# Access_System_Bmduino_V1_2.net
KiCad netlist of a schematic drawn in Altium Designer
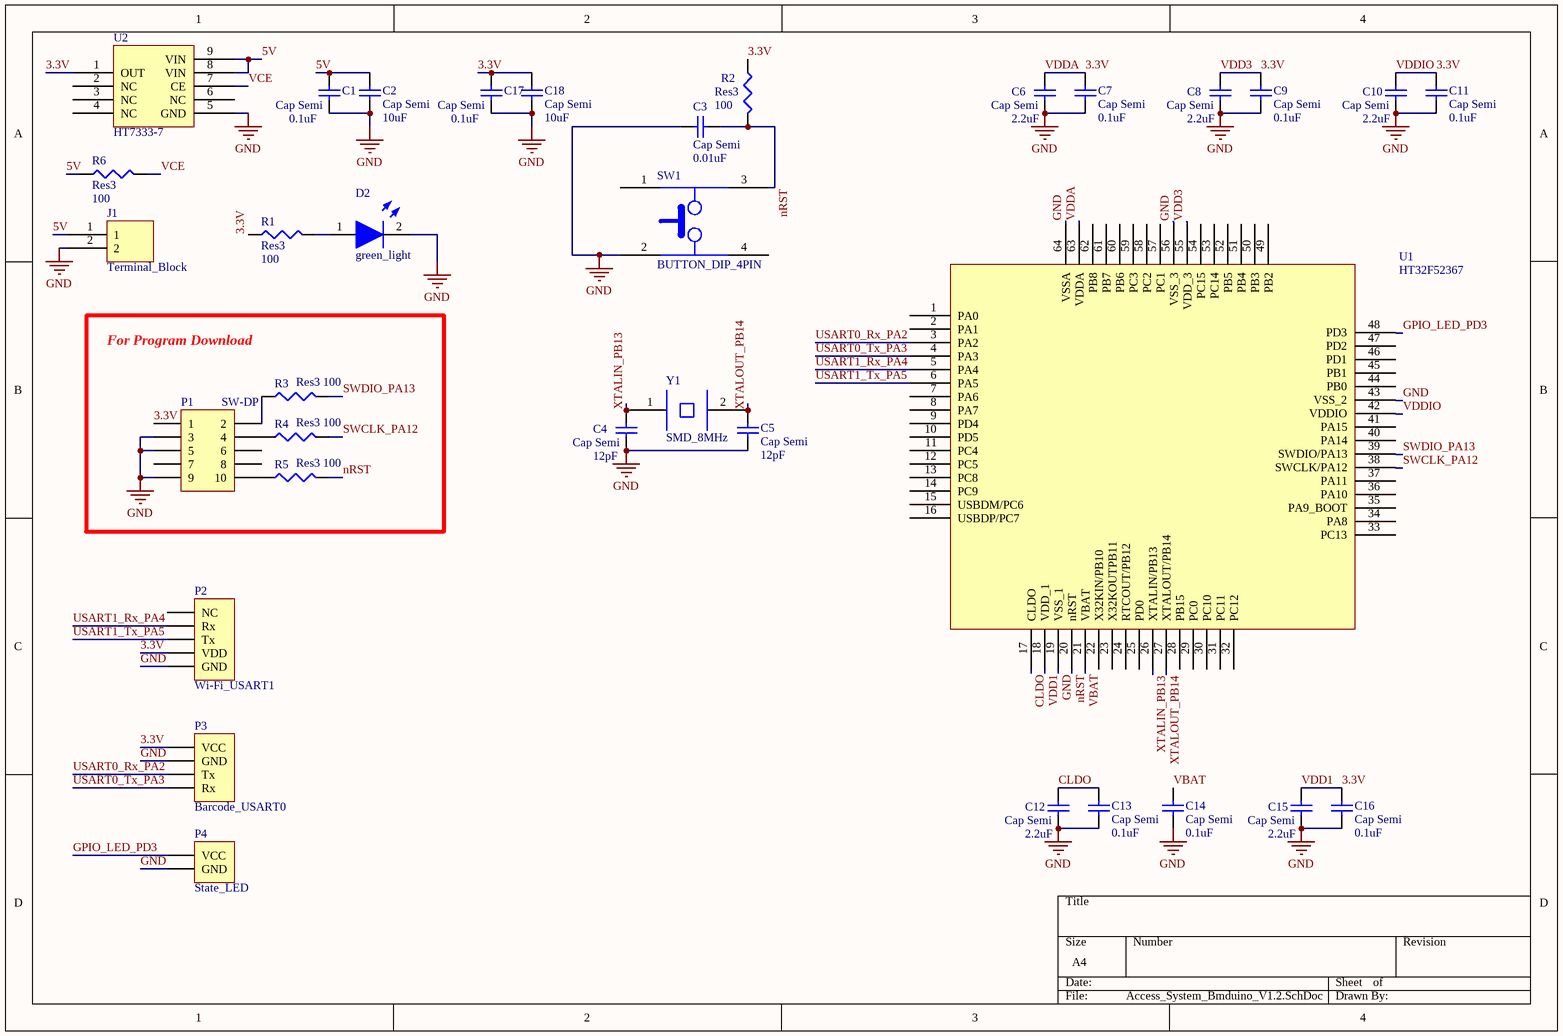
[diagram p0: Access_System_Bmduino_V1.2.SchDoc]

(export (version "E")
  (design (tool "Eeschema 10.0.6"))
  (components
    (comp (ref "C1")
      (value "Cap Semi")
      (footprint "1608[0603]")
      (description "Capacitor (Semiconductor SIM Model)")
      (fields (field (name "ALTIUM_VALUE") "0.1uF") (field (name "PUBLISHER") "Altium Limited"))
      (libsource (lib "Miscellaneous Devices") (part "Cap Semi"))
    )
    (comp (ref "C2")
      (value "Cap Semi")
      (footprint "1608[0603]")
      (description "Capacitor (Semiconductor SIM Model)")
      (fields (field (name "ALTIUM_VALUE") "10uF") (field (name "PUBLISHER") "Altium Limited"))
      (libsource (lib "Miscellaneous Devices") (part "Cap Semi"))
    )
    (comp (ref "C3")
      (value "Cap Semi")
      (footprint "1608[0603]")
      (description "Capacitor (Semiconductor SIM Model)")
      (fields (field (name "ALTIUM_VALUE") "0.01uF") (field (name "PUBLISHER") "Altium Limited"))
      (libsource (lib "Miscellaneous Devices") (part "Cap Semi"))
    )
    (comp (ref "C4")
      (value "Cap Semi")
      (footprint "1608[0603]")
      (description "Capacitor (Semiconductor SIM Model)")
      (fields (field (name "ALTIUM_VALUE") "12pF") (field (name "PUBLISHER") "Altium Limited"))
      (libsource (lib "Miscellaneous Devices") (part "Cap Semi"))
    )
    (comp (ref "C5")
      (value "Cap Semi")
      (footprint "1608[0603]")
      (description "Capacitor (Semiconductor SIM Model)")
      (fields (field (name "ALTIUM_VALUE") "12pF") (field (name "PUBLISHER") "Altium Limited"))
      (libsource (lib "Miscellaneous Devices") (part "Cap Semi"))
    )
    (comp (ref "C6")
      (value "Cap Semi")
      (footprint "1608[0603]")
      (description "Capacitor (Semiconductor SIM Model)")
      (fields (field (name "ALTIUM_VALUE") "2.2uF") (field (name "PUBLISHER") "Altium Limited"))
      (libsource (lib "Miscellaneous Devices") (part "Cap Semi"))
    )
    (comp (ref "C7")
      (value "Cap Semi")
      (footprint "1608[0603]")
      (description "Capacitor (Semiconductor SIM Model)")
      (fields (field (name "ALTIUM_VALUE") "0.1uF") (field (name "PUBLISHER") "Altium Limited"))
      (libsource (lib "Miscellaneous Devices") (part "Cap Semi"))
    )
    (comp (ref "C8")
      (value "Cap Semi")
      (footprint "1608[0603]")
      (description "Capacitor (Semiconductor SIM Model)")
      (fields (field (name "ALTIUM_VALUE") "2.2uF") (field (name "PUBLISHER") "Altium Limited"))
      (libsource (lib "Miscellaneous Devices") (part "Cap Semi"))
    )
    (comp (ref "C9")
      (value "Cap Semi")
      (footprint "1608[0603]")
      (description "Capacitor (Semiconductor SIM Model)")
      (fields (field (name "ALTIUM_VALUE") "0.1uF") (field (name "PUBLISHER") "Altium Limited"))
      (libsource (lib "Miscellaneous Devices") (part "Cap Semi"))
    )
    (comp (ref "C10")
      (value "Cap Semi")
      (footprint "1608[0603]")
      (description "Capacitor (Semiconductor SIM Model)")
      (fields (field (name "ALTIUM_VALUE") "2.2uF") (field (name "PUBLISHER") "Altium Limited"))
      (libsource (lib "Miscellaneous Devices") (part "Cap Semi"))
    )
    (comp (ref "C11")
      (value "Cap Semi")
      (footprint "1608[0603]")
      (description "Capacitor (Semiconductor SIM Model)")
      (fields (field (name "ALTIUM_VALUE") "0.1uF") (field (name "PUBLISHER") "Altium Limited"))
      (libsource (lib "Miscellaneous Devices") (part "Cap Semi"))
    )
    (comp (ref "C12")
      (value "Cap Semi")
      (footprint "1608[0603]")
      (description "Capacitor (Semiconductor SIM Model)")
      (fields (field (name "ALTIUM_VALUE") "2.2uF") (field (name "PUBLISHER") "Altium Limited"))
      (libsource (lib "Miscellaneous Devices") (part "Cap Semi"))
    )
    (comp (ref "C13")
      (value "Cap Semi")
      (footprint "1608[0603]")
      (description "Capacitor (Semiconductor SIM Model)")
      (fields (field (name "ALTIUM_VALUE") "0.1uF") (field (name "PUBLISHER") "Altium Limited"))
      (libsource (lib "Miscellaneous Devices") (part "Cap Semi"))
    )
    (comp (ref "C14")
      (value "Cap Semi")
      (footprint "1608[0603]")
      (description "Capacitor (Semiconductor SIM Model)")
      (fields (field (name "ALTIUM_VALUE") "0.1uF") (field (name "PUBLISHER") "Altium Limited"))
      (libsource (lib "Miscellaneous Devices") (part "Cap Semi"))
    )
    (comp (ref "C15")
      (value "Cap Semi")
      (footprint "1608[0603]")
      (description "Capacitor (Semiconductor SIM Model)")
      (fields (field (name "ALTIUM_VALUE") "2.2uF") (field (name "PUBLISHER") "Altium Limited"))
      (libsource (lib "Miscellaneous Devices") (part "Cap Semi"))
    )
    (comp (ref "C16")
      (value "Cap Semi")
      (footprint "1608[0603]")
      (description "Capacitor (Semiconductor SIM Model)")
      (fields (field (name "ALTIUM_VALUE") "0.1uF") (field (name "PUBLISHER") "Altium Limited"))
      (libsource (lib "Miscellaneous Devices") (part "Cap Semi"))
    )
    (comp (ref "C17")
      (value "Cap Semi")
      (footprint "1608[0603]")
      (description "Capacitor (Semiconductor SIM Model)")
      (fields (field (name "ALTIUM_VALUE") "0.1uF") (field (name "PUBLISHER") "Altium Limited"))
      (libsource (lib "Miscellaneous Devices") (part "Cap Semi"))
    )
    (comp (ref "C18")
      (value "Cap Semi")
      (footprint "1608[0603]")
      (description "Capacitor (Semiconductor SIM Model)")
      (fields (field (name "ALTIUM_VALUE") "10uF") (field (name "PUBLISHER") "Altium Limited"))
      (libsource (lib "Miscellaneous Devices") (part "Cap Semi"))
    )
    (comp (ref "D2")
      (value "green_light")
      (footprint "LED_Green")
      (libsource (lib "Lab_share") (part "LED_Green"))
    )
    (comp (ref "J1")
      (value "Terminal_Block")
      (footprint "terminal block")
      (libsource (lib "Lab_share") (part "Terminal Block"))
    )
    (comp (ref "P1")
      (value "SW-DP")
      (footprint "HDR2X5")
      (description "Header, 5-Pin, Dual row")
      (fields (field (name "PUBLISHER") "Altium Limited"))
      (libsource (lib "Miscellaneous Connectors") (part "Header 5X2"))
    )
    (comp (ref "P2")
      (value "Wi-Fi_USART1")
      (footprint "HDR1X5")
      (description "Header, 5-Pin")
      (fields (field (name "PUBLISHER") "Altium Limited"))
      (libsource (lib "Miscellaneous Connectors") (part "Header 5"))
    )
    (comp (ref "P3")
      (value "Barcode_USART0")
      (footprint "HDR1X4")
      (description "Header, 4-Pin")
      (fields (field (name "PUBLISHER") "Altium Limited"))
      (libsource (lib "Miscellaneous Connectors") (part "Header 4"))
    )
    (comp (ref "P4")
      (value "State_LED")
      (footprint "HDR1X2")
      (description "Header, 2-Pin")
      (fields (field (name "PUBLISHER") "Altium Limited"))
      (libsource (lib "Miscellaneous Connectors") (part "Header 2"))
    )
    (comp (ref "R1")
      (value "Res3")
      (footprint "J1-0603")
      (description "Resistor")
      (fields (field (name "ALTIUM_VALUE") "100") (field (name "PUBLISHER") "Altium Limited"))
      (libsource (lib "Miscellaneous Devices") (part "Res3"))
    )
    (comp (ref "R2")
      (value "Res3")
      (footprint "J1-0603")
      (description "Resistor")
      (fields (field (name "ALTIUM_VALUE") "100") (field (name "PUBLISHER") "Altium Limited"))
      (libsource (lib "Miscellaneous Devices") (part "Res3"))
    )
    (comp (ref "R3")
      (value "Res3")
      (footprint "J1-0603")
      (description "Resistor")
      (fields (field (name "ALTIUM_VALUE") "100") (field (name "PUBLISHER") "Altium Limited"))
      (libsource (lib "Miscellaneous Devices") (part "Res3"))
    )
    (comp (ref "R4")
      (value "Res3")
      (footprint "J1-0603")
      (description "Resistor")
      (fields (field (name "ALTIUM_VALUE") "100") (field (name "PUBLISHER") "Altium Limited"))
      (libsource (lib "Miscellaneous Devices") (part "Res3"))
    )
    (comp (ref "R5")
      (value "Res3")
      (footprint "J1-0603")
      (description "Resistor")
      (fields (field (name "ALTIUM_VALUE") "100") (field (name "PUBLISHER") "Altium Limited"))
      (libsource (lib "Miscellaneous Devices") (part "Res3"))
    )
    (comp (ref "R6")
      (value "Res3")
      (footprint "J1-0603")
      (description "Resistor")
      (fields (field (name "ALTIUM_VALUE") "100") (field (name "PUBLISHER") "Altium Limited"))
      (libsource (lib "Miscellaneous Devices") (part "Res3"))
    )
    (comp (ref "SW1")
      (value "BUTTON_DIP_4PIN")
      (footprint "Push_Button")
      (libsource (lib "Lab_share") (part "Push_Button"))
    )
    (comp (ref "U1")
      (value "HT32F52367")
      (footprint "HT32H52367")
      (libsource (lib "Lab_share") (part "HT32F52367"))
    )
    (comp (ref "U2") (value "HT7333-7") (footprint "HT7333") (libsource (lib "Lab_share") (part "HT7333")))
    (comp (ref "Y1")
      (value "SMD_8MHz")
      (footprint "Quartz-Crystal-8MHz")
      (libsource (lib "Lab_share") (part "Quartz_Crystal_8MHz"))
    )
  )
  (nets
    (net (code "1") (name "/3.3V") (class "Default")
      (node (ref "C10") (pin "1") (pinfunction "1_1") (pintype "passive"))
      (node (ref "C11") (pin "2") (pinfunction "2_2") (pintype "passive"))
      (node (ref "C15") (pin "1") (pinfunction "1_1") (pintype "passive"))
      (node (ref "C16") (pin "2") (pinfunction "2_2") (pintype "passive"))
      (node (ref "C17") (pin "2") (pinfunction "2_2") (pintype "passive"))
      (node (ref "C18") (pin "2") (pinfunction "2_2") (pintype "passive"))
      (node (ref "C6") (pin "1") (pinfunction "1_1") (pintype "passive"))
      (node (ref "C7") (pin "2") (pinfunction "2_2") (pintype "passive"))
      (node (ref "C8") (pin "1") (pinfunction "1_1") (pintype "passive"))
      (node (ref "C9") (pin "2") (pinfunction "2_2") (pintype "passive"))
      (node (ref "P1") (pin "1") (pinfunction "1_1") (pintype "passive"))
      (node (ref "P2") (pin "4") (pinfunction "VDD_4") (pintype "passive"))
      (node (ref "P3") (pin "1") (pinfunction "VCC_1") (pintype "passive"))
      (node (ref "R1") (pin "1") (pinfunction "1_1") (pintype "passive"))
      (node (ref "R2") (pin "1") (pinfunction "1_1") (pintype "passive"))
      (node (ref "U1") (pin "18") (pinfunction "VDD_1_18") (pintype "passive"))
      (node (ref "U1") (pin "42") (pinfunction "VDDIO_42") (pintype "passive"))
      (node (ref "U1") (pin "55") (pinfunction "VDD_3_55") (pintype "passive"))
      (node (ref "U1") (pin "63") (pinfunction "VDDA_63") (pintype "passive"))
      (node (ref "U2") (pin "1") (pinfunction "OUT_1") (pintype "passive"))
    )
    (net (code "2") (name "/5V") (class "Default")
      (node (ref "C1") (pin "2") (pinfunction "2_2") (pintype "passive"))
      (node (ref "C2") (pin "2") (pinfunction "2_2") (pintype "passive"))
      (node (ref "J1") (pin "1") (pinfunction "1_1") (pintype "passive"))
      (node (ref "R6") (pin "1") (pinfunction "1_1") (pintype "passive"))
      (node (ref "U2") (pin "8") (pinfunction "VIN_8") (pintype "passive"))
      (node (ref "U2") (pin "9") (pinfunction "VIN_9") (pintype "passive"))
    )
    (net (code "3") (name "/CLDO") (class "Default")
      (node (ref "C12") (pin "1") (pinfunction "1_1") (pintype "passive"))
      (node (ref "C13") (pin "2") (pinfunction "2_2") (pintype "passive"))
      (node (ref "U1") (pin "17") (pinfunction "CLDO_17") (pintype "passive"))
    )
    (net (code "4") (name "/GPIO_LED_PD3") (class "Default")
      (node (ref "P4") (pin "1") (pinfunction "VCC_1") (pintype "passive"))
      (node (ref "U1") (pin "48") (pinfunction "PD3_48") (pintype "passive"))
    )
    (net (code "5") (name "/SWCLK_PA12") (class "Default")
      (node (ref "R4") (pin "2") (pinfunction "2_2") (pintype "passive"))
      (node (ref "U1") (pin "38") (pinfunction "SWCLK/PA12_38") (pintype "passive"))
    )
    (net (code "6") (name "/SWDIO_PA13") (class "Default")
      (node (ref "R3") (pin "2") (pinfunction "2_2") (pintype "passive"))
      (node (ref "U1") (pin "39") (pinfunction "SWDIO/PA13_39") (pintype "passive"))
    )
    (net (code "7") (name "/USART0_Rx_PA2") (class "Default")
      (node (ref "P3") (pin "3") (pinfunction "Tx_3") (pintype "passive"))
      (node (ref "U1") (pin "3") (pinfunction "PA2_3") (pintype "passive"))
    )
    (net (code "8") (name "/USART0_Tx_PA3") (class "Default")
      (node (ref "P3") (pin "4") (pinfunction "Rx_4") (pintype "passive"))
      (node (ref "U1") (pin "4") (pinfunction "PA3_4") (pintype "passive"))
    )
    (net (code "9") (name "/USART1_Rx_PA4") (class "Default")
      (node (ref "P2") (pin "2") (pinfunction "Rx_2") (pintype "passive"))
      (node (ref "U1") (pin "5") (pinfunction "PA4_5") (pintype "passive"))
    )
    (net (code "10") (name "/USART1_Tx_PA5") (class "Default")
      (node (ref "P2") (pin "3") (pinfunction "Tx_3") (pintype "passive"))
      (node (ref "U1") (pin "6") (pinfunction "PA5_6") (pintype "passive"))
    )
    (net (code "11") (name "/VBAT") (class "Default")
      (node (ref "C14") (pin "2") (pinfunction "2_2") (pintype "passive"))
      (node (ref "U1") (pin "21") (pinfunction "VBAT_21") (pintype "passive"))
    )
    (net (code "12") (name "/VCE") (class "Default")
      (node (ref "R6") (pin "2") (pinfunction "2_2") (pintype "passive"))
      (node (ref "U2") (pin "7") (pinfunction "CE_7") (pintype "passive"))
    )
    (net (code "13") (name "/XTALIN_PB13") (class "Default")
      (node (ref "C4") (pin "1") (pinfunction "1_1") (pintype "passive"))
      (node (ref "U1") (pin "26") (pinfunction "XTALIN/PB13_26") (pintype "passive"))
      (node (ref "Y1") (pin "1") (pintype "passive"))
    )
    (net (code "14") (name "/XTALOUT_PB14") (class "Default")
      (node (ref "C5") (pin "2") (pinfunction "2_2") (pintype "passive"))
      (node (ref "U1") (pin "27") (pinfunction "XTALOUT/PB14_27") (pintype "passive"))
      (node (ref "Y1") (pin "2") (pintype "passive"))
    )
    (net (code "15") (name "/nRST") (class "Default")
      (node (ref "C3") (pin "1") (pinfunction "1_1") (pintype "passive"))
      (node (ref "R2") (pin "2") (pinfunction "2_2") (pintype "passive"))
      (node (ref "R5") (pin "2") (pinfunction "2_2") (pintype "passive"))
      (node (ref "SW1") (pin "3") (pintype "passive"))
      (node (ref "U1") (pin "20") (pinfunction "nRST_20") (pintype "passive"))
    )
    (net (code "16") (name "GND") (class "Default")
      (node (ref "C1") (pin "1") (pinfunction "1_1") (pintype "passive"))
      (node (ref "C10") (pin "2") (pinfunction "2_2") (pintype "passive"))
      (node (ref "C11") (pin "1") (pinfunction "1_1") (pintype "passive"))
      (node (ref "C12") (pin "2") (pinfunction "2_2") (pintype "passive"))
      (node (ref "C13") (pin "1") (pinfunction "1_1") (pintype "passive"))
      (node (ref "C14") (pin "1") (pinfunction "1_1") (pintype "passive"))
      (node (ref "C15") (pin "2") (pinfunction "2_2") (pintype "passive"))
      (node (ref "C16") (pin "1") (pinfunction "1_1") (pintype "passive"))
      (node (ref "C17") (pin "1") (pinfunction "1_1") (pintype "passive"))
      (node (ref "C18") (pin "1") (pinfunction "1_1") (pintype "passive"))
      (node (ref "C2") (pin "1") (pinfunction "1_1") (pintype "passive"))
      (node (ref "C3") (pin "2") (pinfunction "2_2") (pintype "passive"))
      (node (ref "C4") (pin "2") (pinfunction "2_2") (pintype "passive"))
      (node (ref "C5") (pin "1") (pinfunction "1_1") (pintype "passive"))
      (node (ref "C6") (pin "2") (pinfunction "2_2") (pintype "passive"))
      (node (ref "C7") (pin "1") (pinfunction "1_1") (pintype "passive"))
      (node (ref "C8") (pin "2") (pinfunction "2_2") (pintype "passive"))
      (node (ref "C9") (pin "1") (pinfunction "1_1") (pintype "passive"))
      (node (ref "D2") (pin "2") (pintype "passive"))
      (node (ref "J1") (pin "2") (pinfunction "2_2") (pintype "passive"))
      (node (ref "P1") (pin "3") (pinfunction "3_3") (pintype "passive"))
      (node (ref "P1") (pin "5") (pinfunction "5_5") (pintype "passive"))
      (node (ref "P1") (pin "9") (pinfunction "9_9") (pintype "passive"))
      (node (ref "P2") (pin "5") (pinfunction "GND_5") (pintype "passive"))
      (node (ref "P3") (pin "2") (pinfunction "GND_2") (pintype "passive"))
      (node (ref "P4") (pin "2") (pinfunction "GND_2") (pintype "passive"))
      (node (ref "SW1") (pin "2") (pintype "passive"))
      (node (ref "U1") (pin "19") (pinfunction "VSS_1_19") (pintype "passive"))
      (node (ref "U1") (pin "43") (pinfunction "VSS_2_43") (pintype "passive"))
      (node (ref "U1") (pin "56") (pinfunction "VSS_3_56") (pintype "passive"))
      (node (ref "U1") (pin "64") (pinfunction "VSSA_64") (pintype "passive"))
      (node (ref "U2") (pin "5") (pinfunction "GND_5") (pintype "passive"))
    )
    (net (code "17") (name "Net-(D2-Pad1)") (class "Default")
      (node (ref "D2") (pin "1") (pintype "passive"))
      (node (ref "R1") (pin "2") (pinfunction "2_2") (pintype "passive"))
    )
    (net (code "18") (name "Net-(P1-Pad2)") (class "Default")
      (node (ref "P1") (pin "2") (pinfunction "2_2") (pintype "passive"))
      (node (ref "R3") (pin "1") (pinfunction "1_1") (pintype "passive"))
    )
    (net (code "19") (name "Net-(P1-Pad4)") (class "Default")
      (node (ref "P1") (pin "4") (pinfunction "4_4") (pintype "passive"))
      (node (ref "R4") (pin "1") (pinfunction "1_1") (pintype "passive"))
    )
    (net (code "20") (name "Net-(P1-Pad10)") (class "Default")
      (node (ref "P1") (pin "10") (pinfunction "10_10") (pintype "passive"))
      (node (ref "R5") (pin "1") (pinfunction "1_1") (pintype "passive"))
    )
    (net (code "21") (name "unconnected-(P1-Pad6)") (class "Default")
      (node (ref "P1") (pin "6") (pinfunction "6_6") (pintype "passive"))
    )
    (net (code "22") (name "unconnected-(P1-Pad7)") (class "Default")
      (node (ref "P1") (pin "7") (pinfunction "7_7") (pintype "passive"))
    )
    (net (code "23") (name "unconnected-(P1-Pad8)") (class "Default")
      (node (ref "P1") (pin "8") (pinfunction "8_8") (pintype "passive"))
    )
    (net (code "24") (name "unconnected-(P2-NC-Pad1)") (class "Default")
      (node (ref "P2") (pin "1") (pinfunction "NC_1") (pintype "passive"))
    )
    (net (code "25") (name "unconnected-(SW1-Pad1)") (class "Default")
      (node (ref "SW1") (pin "1") (pintype "passive"))
    )
    (net (code "26") (name "unconnected-(SW1-Pad4)") (class "Default")
      (node (ref "SW1") (pin "4") (pintype "passive"))
    )
    (net (code "27") (name "unconnected-(U1-PA0-Pad1)") (class "Default")
      (node (ref "U1") (pin "1") (pinfunction "PA0_1") (pintype "passive"))
    )
    (net (code "28") (name "unconnected-(U1-PA1-Pad2)") (class "Default")
      (node (ref "U1") (pin "2") (pinfunction "PA1_2") (pintype "passive"))
    )
    (net (code "29") (name "unconnected-(U1-PA6-Pad7)") (class "Default")
      (node (ref "U1") (pin "7") (pinfunction "PA6_7") (pintype "passive"))
    )
    (net (code "30") (name "unconnected-(U1-PA7-Pad8)") (class "Default")
      (node (ref "U1") (pin "8") (pinfunction "PA7_8") (pintype "passive"))
    )
    (net (code "31") (name "unconnected-(U1-PA8-Pad34)") (class "Default")
      (node (ref "U1") (pin "34") (pinfunction "PA8_34") (pintype "passive"))
    )
    (net (code "32") (name "unconnected-(U1-PA9_BOOT-Pad35)") (class "Default")
      (node (ref "U1") (pin "35") (pinfunction "PA9_BOOT_35") (pintype "passive"))
    )
    (net (code "33") (name "unconnected-(U1-PA10-Pad36)") (class "Default")
      (node (ref "U1") (pin "36") (pinfunction "PA10_36") (pintype "passive"))
    )
    (net (code "34") (name "unconnected-(U1-PA11-Pad37)") (class "Default")
      (node (ref "U1") (pin "37") (pinfunction "PA11_37") (pintype "passive"))
    )
    (net (code "35") (name "unconnected-(U1-PA14-Pad40)") (class "Default")
      (node (ref "U1") (pin "40") (pinfunction "PA14_40") (pintype "passive"))
    )
    (net (code "36") (name "unconnected-(U1-PA15-Pad41)") (class "Default")
      (node (ref "U1") (pin "41") (pinfunction "PA15_41") (pintype "passive"))
    )
    (net (code "37") (name "unconnected-(U1-PB0-Pad44)") (class "Default")
      (node (ref "U1") (pin "44") (pinfunction "PB0_44") (pintype "passive"))
    )
    (net (code "38") (name "unconnected-(U1-PB1-Pad45)") (class "Default")
      (node (ref "U1") (pin "45") (pinfunction "PB1_45") (pintype "passive"))
    )
    (net (code "39") (name "unconnected-(U1-PB2-Pad49)") (class "Default")
      (node (ref "U1") (pin "49") (pinfunction "PB2_49") (pintype "passive"))
    )
    (net (code "40") (name "unconnected-(U1-PB3-Pad50)") (class "Default")
      (node (ref "U1") (pin "50") (pinfunction "PB3_50") (pintype "passive"))
    )
    (net (code "41") (name "unconnected-(U1-PB4-Pad51)") (class "Default")
      (node (ref "U1") (pin "51") (pinfunction "PB4_51") (pintype "passive"))
    )
    (net (code "42") (name "unconnected-(U1-PB5-Pad52)") (class "Default")
      (node (ref "U1") (pin "52") (pinfunction "PB5_52") (pintype "passive"))
    )
    (net (code "43") (name "unconnected-(U1-PB6-Pad60)") (class "Default")
      (node (ref "U1") (pin "60") (pinfunction "PB6_60") (pintype "passive"))
    )
    (net (code "44") (name "unconnected-(U1-PB7-Pad61)") (class "Default")
      (node (ref "U1") (pin "61") (pinfunction "PB7_61") (pintype "passive"))
    )
    (net (code "45") (name "unconnected-(U1-PB8-Pad62)") (class "Default")
      (node (ref "U1") (pin "62") (pinfunction "PB8_62") (pintype "passive"))
    )
    (net (code "46") (name "unconnected-(U1-PB15-Pad28)") (class "Default")
      (node (ref "U1") (pin "28") (pinfunction "PB15_28") (pintype "passive"))
    )
    (net (code "47") (name "unconnected-(U1-PC0-Pad29)") (class "Default")
      (node (ref "U1") (pin "29") (pinfunction "PC0_29") (pintype "passive"))
    )
    (net (code "48") (name "unconnected-(U1-PC1-Pad57)") (class "Default")
      (node (ref "U1") (pin "57") (pinfunction "PC1_57") (pintype "passive"))
    )
    (net (code "49") (name "unconnected-(U1-PC2-Pad58)") (class "Default")
      (node (ref "U1") (pin "58") (pinfunction "PC2_58") (pintype "passive"))
    )
    (net (code "50") (name "unconnected-(U1-PC3-Pad59)") (class "Default")
      (node (ref "U1") (pin "59") (pinfunction "PC3_59") (pintype "passive"))
    )
    (net (code "51") (name "unconnected-(U1-PC4-Pad11)") (class "Default")
      (node (ref "U1") (pin "11") (pinfunction "PC4_11") (pintype "passive"))
    )
    (net (code "52") (name "unconnected-(U1-PC5-Pad12)") (class "Default")
      (node (ref "U1") (pin "12") (pinfunction "PC5_12") (pintype "passive"))
    )
    (net (code "53") (name "unconnected-(U1-PC8-Pad13)") (class "Default")
      (node (ref "U1") (pin "13") (pinfunction "PC8_13") (pintype "passive"))
    )
    (net (code "54") (name "unconnected-(U1-PC9-Pad14)") (class "Default")
      (node (ref "U1") (pin "14") (pinfunction "PC9_14") (pintype "passive"))
    )
    (net (code "55") (name "unconnected-(U1-PC10-Pad30)") (class "Default")
      (node (ref "U1") (pin "30") (pinfunction "PC10_30") (pintype "passive"))
    )
    (net (code "56") (name "unconnected-(U1-PC11-Pad31)") (class "Default")
      (node (ref "U1") (pin "31") (pinfunction "PC11_31") (pintype "passive"))
    )
    (net (code "57") (name "unconnected-(U1-PC12-Pad32)") (class "Default")
      (node (ref "U1") (pin "32") (pinfunction "PC12_32") (pintype "passive"))
    )
    (net (code "58") (name "unconnected-(U1-PC13-Pad33)") (class "Default")
      (node (ref "U1") (pin "33") (pinfunction "PC13_33") (pintype "passive"))
    )
    (net (code "59") (name "unconnected-(U1-PC14-Pad53)") (class "Default")
      (node (ref "U1") (pin "53") (pinfunction "PC14_53") (pintype "passive"))
    )
    (net (code "60") (name "unconnected-(U1-PC15-Pad54)") (class "Default")
      (node (ref "U1") (pin "54") (pinfunction "PC15_54") (pintype "passive"))
    )
    (net (code "61") (name "unconnected-(U1-PD0-Pad25)") (class "Default")
      (node (ref "U1") (pin "25") (pinfunction "PD0_25") (pintype "passive"))
    )
    (net (code "62") (name "unconnected-(U1-PD1-Pad46)") (class "Default")
      (node (ref "U1") (pin "46") (pinfunction "PD1_46") (pintype "passive"))
    )
    (net (code "63") (name "unconnected-(U1-PD2-Pad47)") (class "Default")
      (node (ref "U1") (pin "47") (pinfunction "PD2_47") (pintype "passive"))
    )
    (net (code "64") (name "unconnected-(U1-PD4-Pad9)") (class "Default")
      (node (ref "U1") (pin "9") (pinfunction "PD4_9") (pintype "passive"))
    )
    (net (code "65") (name "unconnected-(U1-PD5-Pad10)") (class "Default")
      (node (ref "U1") (pin "10") (pinfunction "PD5_10") (pintype "passive"))
    )
    (net (code "66") (name "unconnected-(U1-RTCOUT{slash}PB12-Pad24)") (class "Default")
      (node (ref "U1") (pin "24") (pinfunction "RTCOUT/PB12_24") (pintype "passive"))
    )
    (net (code "67") (name "unconnected-(U1-USBDM{slash}PC6-Pad15)") (class "Default")
      (node (ref "U1") (pin "15") (pinfunction "USBDM/PC6_15") (pintype "passive"))
    )
    (net (code "68") (name "unconnected-(U1-USBDP{slash}PC7-Pad16)") (class "Default")
      (node (ref "U1") (pin "16") (pinfunction "USBDP/PC7_16") (pintype "passive"))
    )
    (net (code "69") (name "unconnected-(U1-X32KIN{slash}PB10-Pad22)") (class "Default")
      (node (ref "U1") (pin "22") (pinfunction "X32KIN/PB10_22") (pintype "passive"))
    )
    (net (code "70") (name "unconnected-(U1-X32KOUTPB11-Pad23)") (class "Default")
      (node (ref "U1") (pin "23") (pinfunction "X32KOUTPB11_23") (pintype "passive"))
    )
    (net (code "71") (name "unconnected-(U2-NC-Pad2)") (class "Default")
      (node (ref "U2") (pin "2") (pinfunction "NC_2") (pintype "passive"))
    )
    (net (code "72") (name "unconnected-(U2-NC-Pad3)") (class "Default")
      (node (ref "U2") (pin "3") (pinfunction "NC_3") (pintype "passive"))
    )
    (net (code "73") (name "unconnected-(U2-NC-Pad4)") (class "Default")
      (node (ref "U2") (pin "4") (pinfunction "NC_4") (pintype "passive"))
    )
    (net (code "74") (name "unconnected-(U2-NC-Pad6)") (class "Default")
      (node (ref "U2") (pin "6") (pinfunction "NC_6") (pintype "passive"))
    )
  )
)
